# light_switch_smd3.net
KiCad netlist of a schematic drawn in EAGLE
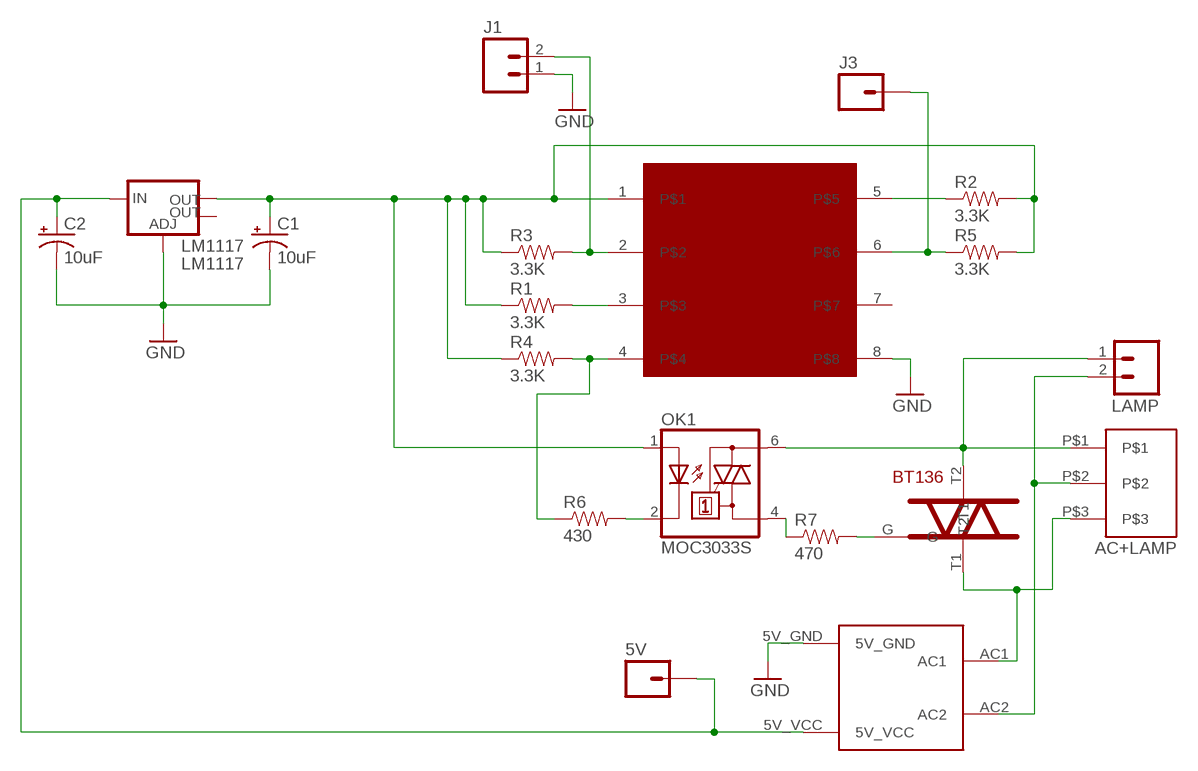
[diagram p0: schematic, sheet 1]

(export (version "E")
  (design (tool "Eeschema 10.0.6"))
  (components
    (comp (ref "5V")
      (value "M01PTH")
      (footprint "eagle-import:1X01")
      (libsource (lib "eagle-import") (part "M01PTH"))
    )
    (comp (ref "AC+LAMP")
      (value "DG350-3.5-03P")
      (footprint "eagle-import:DG350-3.5-03P")
      (libsource (lib "eagle-import") (part "DG350-3.5-03P"))
    )
    (comp (ref "BT136")
      (value "BT136")
      (footprint "eagle-import:BT136-PKG")
      (libsource (lib "eagle-import") (part "BT136"))
    )
    (comp (ref "C1")
      (value "10uF")
      (footprint "eagle-import:0603-POL")
      (libsource (lib "eagle-import") (part "10UF-6.3V-20%(0603)(TANT){dblquote}"))
    )
    (comp (ref "C2")
      (value "10uF")
      (footprint "eagle-import:0603-POL")
      (libsource (lib "eagle-import") (part "10UF-6.3V-20%(0603)(TANT){dblquote}"))
    )
    (comp (ref "J1")
      (value "M02PTH")
      (footprint "eagle-import:1X02")
      (libsource (lib "eagle-import") (part "M02PTH"))
    )
    (comp (ref "J3")
      (value "M01PTH")
      (footprint "eagle-import:1X01")
      (libsource (lib "eagle-import") (part "M01PTH"))
    )
    (comp (ref "LAMP")
      (value "M02PTH")
      (footprint "eagle-import:1X02")
      (libsource (lib "eagle-import") (part "M02PTH"))
    )
    (comp (ref "LM1117")
      (value "LM1117")
      (footprint "eagle-import:SOT223")
      (libsource (lib "eagle-import") (part "V_REG_LM1117SOT223"))
    )
    (comp (ref "OK1")
      (value "MOC3033S")
      (footprint "eagle-import:DIL6-SMD")
      (fields (field (name "MF") "FAIRCHILD SEMICONDUCTOR") (field (name "MPN") "MOC3033S-M"))
      (libsource (lib "eagle-import") (part "MOC30S33"))
    )
    (comp (ref "R1")
      (value "3.3K")
      (footprint "eagle-import:0603-RES")
      (libsource (lib "eagle-import") (part "3.3MOHM-1/10W-1%(0603)"))
    )
    (comp (ref "R2")
      (value "3.3K")
      (footprint "eagle-import:0603-RES")
      (libsource (lib "eagle-import") (part "3.3MOHM-1/10W-1%(0603)"))
    )
    (comp (ref "R3")
      (value "3.3K")
      (footprint "eagle-import:0603-RES")
      (libsource (lib "eagle-import") (part "3.3MOHM-1/10W-1%(0603)"))
    )
    (comp (ref "R4")
      (value "3.3K")
      (footprint "eagle-import:0603-RES")
      (libsource (lib "eagle-import") (part "3.3MOHM-1/10W-1%(0603)"))
    )
    (comp (ref "R5")
      (value "3.3K")
      (footprint "eagle-import:0603-RES")
      (libsource (lib "eagle-import") (part "3.3MOHM-1/10W-1%(0603)"))
    )
    (comp (ref "R6")
      (value "430")
      (footprint "eagle-import:0603-RES")
      (libsource (lib "eagle-import") (part "RESISTOR0603"))
    )
    (comp (ref "R7")
      (value "470")
      (footprint "eagle-import:0603-RES")
      (libsource (lib "eagle-import") (part "RESISTOR0603"))
    )
    (comp (ref "U$1")
      (value "HI-LINK5V-ACDC")
      (footprint "eagle-import:AC5V")
      (libsource (lib "eagle-import") (part "HI-LINK5V-ACDC"))
    )
    (comp (ref "U$2")
      (value "ESP8266-01")
      (footprint "eagle-import:ESP8266-01")
      (libsource (lib "eagle-import") (part "ESP8266-01"))
    )
  )
  (nets
    (net (code "1") (name "GND") (class "Default")
      (node (ref "C1") (pin "K") (pinfunction "-_K") (pintype "passive"))
      (node (ref "C2") (pin "K") (pinfunction "-_K") (pintype "passive"))
      (node (ref "J1") (pin "1") (pinfunction "1_1") (pintype "passive"))
      (node (ref "LM1117") (pin "1") (pinfunction "ADJ_1") (pintype "input"))
      (node (ref "U$1") (pin "5V_GND") (pinfunction "5V_GND_5V_GND") (pintype "bidirectional"))
      (node (ref "U$2") (pin "8") (pinfunction "P$8_8") (pintype "bidirectional"))
    )
    (net (code "2") (name "Net-(AC+LAMP-PadP$2)") (class "Default")
      (node (ref "AC+LAMP") (pin "P$2") (pinfunction "P$2_P$2") (pintype "bidirectional"))
      (node (ref "LAMP") (pin "2") (pinfunction "2_2") (pintype "passive"))
      (node (ref "U$1") (pin "AC2") (pinfunction "AC2_AC2") (pintype "bidirectional"))
    )
    (net (code "3") (name "Net-(AC+LAMP-PadP$3)") (class "Default")
      (node (ref "AC+LAMP") (pin "P$3") (pinfunction "P$3_P$3") (pintype "bidirectional"))
      (node (ref "BT136") (pin "T1") (pinfunction "T1_T1") (pintype "bidirectional"))
      (node (ref "U$1") (pin "AC1") (pinfunction "AC1_AC1") (pintype "bidirectional"))
    )
    (net (code "4") (name "Net-(BT136-PadG)") (class "Default")
      (node (ref "BT136") (pin "G") (pinfunction "G_G") (pintype "bidirectional"))
      (node (ref "R7") (pin "2") (pinfunction "2_2") (pintype "passive"))
    )
    (net (code "5") (name "Net-(C1-+)") (class "Default")
      (node (ref "C1") (pin "A") (pinfunction "+_A") (pintype "passive"))
      (node (ref "LM1117") (pin "2") (pinfunction "OUT_2") (pintype "output"))
      (node (ref "OK1") (pin "1") (pinfunction "A_1") (pintype "passive"))
      (node (ref "R1") (pin "1") (pinfunction "1_1") (pintype "passive"))
      (node (ref "R2") (pin "2") (pinfunction "2_2") (pintype "passive"))
      (node (ref "R3") (pin "1") (pinfunction "1_1") (pintype "passive"))
      (node (ref "R4") (pin "1") (pinfunction "1_1") (pintype "passive"))
      (node (ref "R5") (pin "2") (pinfunction "2_2") (pintype "passive"))
      (node (ref "U$2") (pin "1") (pinfunction "P$1_1") (pintype "bidirectional"))
    )
    (net (code "6") (name "Net-(C2-+)") (class "Default")
      (node (ref "5V") (pin "1") (pinfunction "1_1") (pintype "passive"))
      (node (ref "C2") (pin "A") (pinfunction "+_A") (pintype "passive"))
      (node (ref "LM1117") (pin "3") (pinfunction "IN_3") (pintype "input"))
      (node (ref "U$1") (pin "5V_VCC") (pinfunction "5V_VCC_5V_VCC") (pintype "bidirectional"))
    )
    (net (code "7") (name "Net-(OK1-A1)") (class "Default")
      (node (ref "OK1") (pin "4") (pinfunction "A1_4") (pintype "passive"))
      (node (ref "R7") (pin "1") (pinfunction "1_1") (pintype "passive"))
    )
    (net (code "8") (name "Net-(OK1-A2)") (class "Default")
      (node (ref "AC+LAMP") (pin "P$1") (pinfunction "P$1_P$1") (pintype "bidirectional"))
      (node (ref "BT136") (pin "T2") (pinfunction "T2_T2") (pintype "bidirectional"))
      (node (ref "LAMP") (pin "1") (pinfunction "1_1") (pintype "passive"))
      (node (ref "OK1") (pin "6") (pinfunction "A2_6") (pintype "passive"))
    )
    (net (code "9") (name "Net-(OK1-C)") (class "Default")
      (node (ref "OK1") (pin "2") (pinfunction "C_2") (pintype "passive"))
      (node (ref "R6") (pin "2") (pinfunction "2_2") (pintype "passive"))
    )
    (net (code "10") (name "Net-(U$2-P$2)") (class "Default")
      (node (ref "J1") (pin "2") (pinfunction "2_2") (pintype "passive"))
      (node (ref "R3") (pin "2") (pinfunction "2_2") (pintype "passive"))
      (node (ref "U$2") (pin "2") (pinfunction "P$2_2") (pintype "bidirectional"))
    )
    (net (code "11") (name "Net-(U$2-P$3)") (class "Default")
      (node (ref "R1") (pin "2") (pinfunction "2_2") (pintype "passive"))
      (node (ref "U$2") (pin "3") (pinfunction "P$3_3") (pintype "bidirectional"))
    )
    (net (code "12") (name "Net-(U$2-P$4)") (class "Default")
      (node (ref "R4") (pin "2") (pinfunction "2_2") (pintype "passive"))
      (node (ref "R6") (pin "1") (pinfunction "1_1") (pintype "passive"))
      (node (ref "U$2") (pin "4") (pinfunction "P$4_4") (pintype "bidirectional"))
    )
    (net (code "13") (name "Net-(U$2-P$5)") (class "Default")
      (node (ref "R2") (pin "1") (pinfunction "1_1") (pintype "passive"))
      (node (ref "U$2") (pin "5") (pinfunction "P$5_5") (pintype "bidirectional"))
    )
    (net (code "14") (name "Net-(U$2-P$6)") (class "Default")
      (node (ref "J3") (pin "1") (pinfunction "1_1") (pintype "passive"))
      (node (ref "R5") (pin "1") (pinfunction "1_1") (pintype "passive"))
      (node (ref "U$2") (pin "6") (pinfunction "P$6_6") (pintype "bidirectional"))
    )
    (net (code "15") (name "unconnected-(LM1117-OUT-Pad4)") (class "Default")
      (node (ref "LM1117") (pin "4") (pinfunction "OUT_4") (pintype "output"))
    )
    (net (code "16") (name "unconnected-(U$2-P$7-Pad7)") (class "Default")
      (node (ref "U$2") (pin "7") (pinfunction "P$7_7") (pintype "bidirectional"))
    )
  )
)
